# Sheet1.net
KiCad netlist of a schematic drawn in Altium Designer
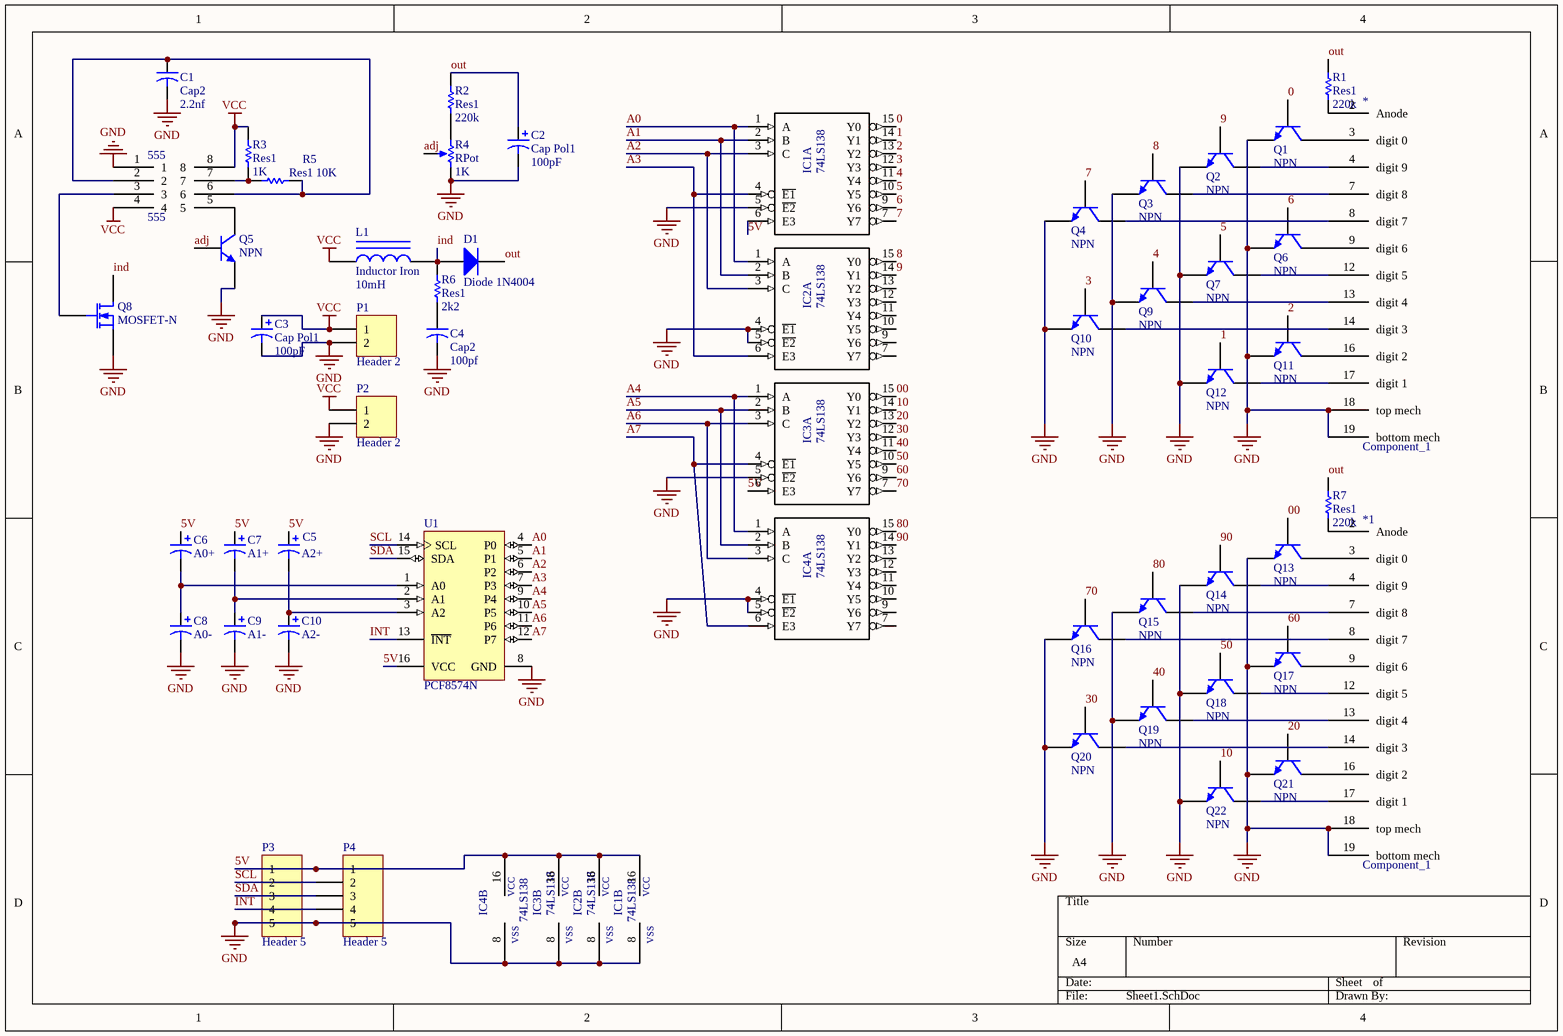
[diagram p0: Sheet1.SchDoc]

(export (version "E")
  (design (tool "Eeschema 10.0.6"))
  (components
    (comp (ref "*")
      (value "Component_1")
      (footprint "B8091")
      (libsource (lib "Schlib1") (part "Component_1"))
    )
    (comp (ref "*1")
      (value "Component_1")
      (footprint "B8091")
      (libsource (lib "Schlib1") (part "Component_1"))
    )
    (comp (ref "555") (value "555") (footprint "555") (libsource (lib "Schlib1") (part "555")))
    (comp (ref "C1")
      (value "Cap2")
      (footprint "CAPR5-4X5")
      (description "Capacitor")
      (fields (field (name "ALTIUM_VALUE") "2.2nf") (field (name "PUBLISHER") "Altium Limited"))
      (libsource (lib "Miscellaneous Devices") (part "Cap2"))
    )
    (comp (ref "C2")
      (value "Cap Pol1")
      (footprint "RB7.6-15")
      (description "Polarized Capacitor (Radial)")
      (fields (field (name "ALTIUM_VALUE") "100pF") (field (name "PUBLISHER") "Altium Limited"))
      (libsource (lib "Miscellaneous Devices") (part "Cap Pol1"))
    )
    (comp (ref "C3")
      (value "Cap Pol1")
      (footprint "RB7.6-15")
      (description "Polarized Capacitor (Radial)")
      (fields (field (name "ALTIUM_VALUE") "100pF") (field (name "PUBLISHER") "Altium Limited"))
      (libsource (lib "Miscellaneous Devices") (part "Cap Pol1"))
    )
    (comp (ref "C4")
      (value "Cap2")
      (footprint "CAPR5-4X5")
      (description "Capacitor")
      (fields (field (name "ALTIUM_VALUE") "100pf") (field (name "PUBLISHER") "Altium Limited"))
      (libsource (lib "Miscellaneous Devices") (part "Cap2"))
    )
    (comp (ref "C5")
      (value "A2+")
      (footprint "C0805")
      (description "Polarized Capacitor (Surface Mount)")
      (fields (field (name "PUBLISHER") "Altium Limited"))
      (libsource (lib "Miscellaneous Devices") (part "Cap Pol3"))
    )
    (comp (ref "C6")
      (value "A0+")
      (footprint "C0805")
      (description "Polarized Capacitor (Surface Mount)")
      (fields (field (name "PUBLISHER") "Altium Limited"))
      (libsource (lib "Miscellaneous Devices") (part "Cap Pol3"))
    )
    (comp (ref "C7")
      (value "A1+")
      (footprint "C0805")
      (description "Polarized Capacitor (Surface Mount)")
      (fields (field (name "PUBLISHER") "Altium Limited"))
      (libsource (lib "Miscellaneous Devices") (part "Cap Pol3"))
    )
    (comp (ref "C8")
      (value "A0-")
      (footprint "C0805")
      (description "Polarized Capacitor (Surface Mount)")
      (fields (field (name "PUBLISHER") "Altium Limited"))
      (libsource (lib "Miscellaneous Devices") (part "Cap Pol3"))
    )
    (comp (ref "C9")
      (value "A1-")
      (footprint "C0805")
      (description "Polarized Capacitor (Surface Mount)")
      (fields (field (name "PUBLISHER") "Altium Limited"))
      (libsource (lib "Miscellaneous Devices") (part "Cap Pol3"))
    )
    (comp (ref "C10")
      (value "A2-")
      (footprint "C0805")
      (description "Polarized Capacitor (Surface Mount)")
      (fields (field (name "PUBLISHER") "Altium Limited"))
      (libsource (lib "Miscellaneous Devices") (part "Cap Pol3"))
    )
    (comp (ref "D1")
      (value "Diode 1N4004")
      (footprint "DO-41")
      (description "1 Amp General Purpose Rectifier")
      (fields (field (name "PUBLISHER") "Altium Limited"))
      (libsource (lib "Miscellaneous Devices") (part "Diode 1N4004"))
    )
    (comp (ref "IC1")
      (value "74LS138")
      (footprint "DIP-16")
      (fields (field (name "MF") "Texas Instruments"))
      (libsource (lib "74LS138") (part "74LS138"))
    )
    (comp (ref "IC2")
      (value "74LS138")
      (footprint "DIP-16")
      (fields (field (name "MF") "Texas Instruments"))
      (libsource (lib "74LS138") (part "74LS138"))
    )
    (comp (ref "IC3")
      (value "74LS138")
      (footprint "DIP-16")
      (fields (field (name "MF") "Texas Instruments"))
      (libsource (lib "74LS138") (part "74LS138"))
    )
    (comp (ref "IC4")
      (value "74LS138")
      (footprint "DIP-16")
      (fields (field (name "MF") "Texas Instruments"))
      (libsource (lib "74LS138") (part "74LS138"))
    )
    (comp (ref "L1")
      (value "Inductor Iron")
      (footprint "AXIAL-0.5")
      (description "Magnetic-Core Inductor")
      (fields (field (name "ALTIUM_VALUE") "10mH") (field (name "PUBLISHER") "Altium Limited"))
      (libsource (lib "Miscellaneous Devices") (part "Inductor Iron"))
    )
    (comp (ref "P1")
      (value "Header 2")
      (footprint "HDR1X2")
      (description "Header, 2-Pin")
      (fields (field (name "PUBLISHER") "Altium Limited"))
      (libsource (lib "Miscellaneous Connectors") (part "Header 2"))
    )
    (comp (ref "P2")
      (value "Header 2")
      (footprint "HDR1X2")
      (description "Header, 2-Pin")
      (fields (field (name "PUBLISHER") "Altium Limited"))
      (libsource (lib "Miscellaneous Connectors") (part "Header 2"))
    )
    (comp (ref "P3")
      (value "Header 5")
      (footprint "HDR1X5")
      (description "Header, 5-Pin")
      (fields (field (name "PUBLISHER") "Altium Limited"))
      (libsource (lib "Miscellaneous Connectors") (part "Header 5"))
    )
    (comp (ref "P4")
      (value "Header 5")
      (footprint "HDR1X5")
      (description "Header, 5-Pin")
      (fields (field (name "PUBLISHER") "Altium Limited"))
      (libsource (lib "Miscellaneous Connectors") (part "Header 5"))
    )
    (comp (ref "Q1")
      (value "NPN")
      (footprint "TO-226-AA")
      (description "NPN Bipolar Transistor")
      (fields (field (name "PUBLISHER") "Altium Limited"))
      (libsource (lib "Miscellaneous Devices") (part "NPN"))
    )
    (comp (ref "Q2")
      (value "NPN")
      (footprint "TO-226-AA")
      (description "NPN Bipolar Transistor")
      (fields (field (name "PUBLISHER") "Altium Limited"))
      (libsource (lib "Miscellaneous Devices") (part "NPN"))
    )
    (comp (ref "Q3")
      (value "NPN")
      (footprint "TO-226-AA")
      (description "NPN Bipolar Transistor")
      (fields (field (name "PUBLISHER") "Altium Limited"))
      (libsource (lib "Miscellaneous Devices") (part "NPN"))
    )
    (comp (ref "Q4")
      (value "NPN")
      (footprint "TO-226-AA")
      (description "NPN Bipolar Transistor")
      (fields (field (name "PUBLISHER") "Altium Limited"))
      (libsource (lib "Miscellaneous Devices") (part "NPN"))
    )
    (comp (ref "Q5")
      (value "NPN")
      (footprint "TO-226-AA")
      (description "NPN Bipolar Transistor")
      (fields (field (name "PUBLISHER") "Altium Limited"))
      (libsource (lib "Miscellaneous Devices") (part "NPN"))
    )
    (comp (ref "Q6")
      (value "NPN")
      (footprint "TO-226-AA")
      (description "NPN Bipolar Transistor")
      (fields (field (name "PUBLISHER") "Altium Limited"))
      (libsource (lib "Miscellaneous Devices") (part "NPN"))
    )
    (comp (ref "Q7")
      (value "NPN")
      (footprint "TO-226-AA")
      (description "NPN Bipolar Transistor")
      (fields (field (name "PUBLISHER") "Altium Limited"))
      (libsource (lib "Miscellaneous Devices") (part "NPN"))
    )
    (comp (ref "Q8")
      (value "MOSFET-N")
      (footprint "E3")
      (description "N-Channel MOSFET")
      (fields (field (name "PUBLISHER") "Altium Limited"))
      (libsource (lib "Miscellaneous Devices") (part "MOSFET-N"))
    )
    (comp (ref "Q9")
      (value "NPN")
      (footprint "TO-226-AA")
      (description "NPN Bipolar Transistor")
      (fields (field (name "PUBLISHER") "Altium Limited"))
      (libsource (lib "Miscellaneous Devices") (part "NPN"))
    )
    (comp (ref "Q10")
      (value "NPN")
      (footprint "TO-226-AA")
      (description "NPN Bipolar Transistor")
      (fields (field (name "PUBLISHER") "Altium Limited"))
      (libsource (lib "Miscellaneous Devices") (part "NPN"))
    )
    (comp (ref "Q11")
      (value "NPN")
      (footprint "TO-226-AA")
      (description "NPN Bipolar Transistor")
      (fields (field (name "PUBLISHER") "Altium Limited"))
      (libsource (lib "Miscellaneous Devices") (part "NPN"))
    )
    (comp (ref "Q12")
      (value "NPN")
      (footprint "TO-226-AA")
      (description "NPN Bipolar Transistor")
      (fields (field (name "PUBLISHER") "Altium Limited"))
      (libsource (lib "Miscellaneous Devices") (part "NPN"))
    )
    (comp (ref "Q13")
      (value "NPN")
      (footprint "TO-226-AA")
      (description "NPN Bipolar Transistor")
      (fields (field (name "PUBLISHER") "Altium Limited"))
      (libsource (lib "Miscellaneous Devices") (part "NPN"))
    )
    (comp (ref "Q14")
      (value "NPN")
      (footprint "TO-226-AA")
      (description "NPN Bipolar Transistor")
      (fields (field (name "PUBLISHER") "Altium Limited"))
      (libsource (lib "Miscellaneous Devices") (part "NPN"))
    )
    (comp (ref "Q15")
      (value "NPN")
      (footprint "TO-226-AA")
      (description "NPN Bipolar Transistor")
      (fields (field (name "PUBLISHER") "Altium Limited"))
      (libsource (lib "Miscellaneous Devices") (part "NPN"))
    )
    (comp (ref "Q16")
      (value "NPN")
      (footprint "TO-226-AA")
      (description "NPN Bipolar Transistor")
      (fields (field (name "PUBLISHER") "Altium Limited"))
      (libsource (lib "Miscellaneous Devices") (part "NPN"))
    )
    (comp (ref "Q17")
      (value "NPN")
      (footprint "TO-226-AA")
      (description "NPN Bipolar Transistor")
      (fields (field (name "PUBLISHER") "Altium Limited"))
      (libsource (lib "Miscellaneous Devices") (part "NPN"))
    )
    (comp (ref "Q18")
      (value "NPN")
      (footprint "TO-226-AA")
      (description "NPN Bipolar Transistor")
      (fields (field (name "PUBLISHER") "Altium Limited"))
      (libsource (lib "Miscellaneous Devices") (part "NPN"))
    )
    (comp (ref "Q19")
      (value "NPN")
      (footprint "TO-226-AA")
      (description "NPN Bipolar Transistor")
      (fields (field (name "PUBLISHER") "Altium Limited"))
      (libsource (lib "Miscellaneous Devices") (part "NPN"))
    )
    (comp (ref "Q20")
      (value "NPN")
      (footprint "TO-226-AA")
      (description "NPN Bipolar Transistor")
      (fields (field (name "PUBLISHER") "Altium Limited"))
      (libsource (lib "Miscellaneous Devices") (part "NPN"))
    )
    (comp (ref "Q21")
      (value "NPN")
      (footprint "TO-226-AA")
      (description "NPN Bipolar Transistor")
      (fields (field (name "PUBLISHER") "Altium Limited"))
      (libsource (lib "Miscellaneous Devices") (part "NPN"))
    )
    (comp (ref "Q22")
      (value "NPN")
      (footprint "TO-226-AA")
      (description "NPN Bipolar Transistor")
      (fields (field (name "PUBLISHER") "Altium Limited"))
      (libsource (lib "Miscellaneous Devices") (part "NPN"))
    )
    (comp (ref "R1")
      (value "Res1")
      (footprint "AXIAL-0.3")
      (description "Resistor")
      (fields (field (name "ALTIUM_VALUE") "220k") (field (name "PUBLISHER") "Altium Limited"))
      (libsource (lib "Miscellaneous Devices") (part "Res1"))
    )
    (comp (ref "R2")
      (value "Res1")
      (footprint "AXIAL-0.3")
      (description "Resistor")
      (fields (field (name "ALTIUM_VALUE") "220k") (field (name "PUBLISHER") "Altium Limited"))
      (libsource (lib "Miscellaneous Devices") (part "Res1"))
    )
    (comp (ref "R3")
      (value "Res1")
      (footprint "AXIAL-0.3")
      (description "Resistor")
      (fields (field (name "ALTIUM_VALUE") "1K") (field (name "PUBLISHER") "Altium Limited"))
      (libsource (lib "Miscellaneous Devices") (part "Res1"))
    )
    (comp (ref "R4")
      (value "RPot")
      (footprint "VR5")
      (description "Potentiometer")
      (fields (field (name "ALTIUM_VALUE") "1K") (field (name "PUBLISHER") "Altium Limited"))
      (libsource (lib "Miscellaneous Devices") (part "RPot"))
    )
    (comp (ref "R5")
      (value "Res1")
      (footprint "AXIAL-0.3")
      (description "Resistor")
      (fields (field (name "ALTIUM_VALUE") "10K") (field (name "PUBLISHER") "Altium Limited"))
      (libsource (lib "Miscellaneous Devices") (part "Res1"))
    )
    (comp (ref "R6")
      (value "Res1")
      (footprint "AXIAL-0.3")
      (description "Resistor")
      (fields (field (name "ALTIUM_VALUE") "2k2") (field (name "PUBLISHER") "Altium Limited"))
      (libsource (lib "Miscellaneous Devices") (part "Res1"))
    )
    (comp (ref "R7")
      (value "Res1")
      (footprint "AXIAL-0.3")
      (description "Resistor")
      (fields (field (name "ALTIUM_VALUE") "220k") (field (name "PUBLISHER") "Altium Limited"))
      (libsource (lib "Miscellaneous Devices") (part "Res1"))
    )
    (comp (ref "U1")
      (value "PCF8574N")
      (footprint "N0016A")
      (description "Remote 8-Bit I/O Expander for I2C-Bus, 2.5 to 6 V, -40 to 85 degC, 16-pin PDIP (N), Pb-Free (RoHS)")
      (fields (field (name "MANUFACTURER") "Texas Instruments"))
      (libsource (lib "Altium Content Vault") (part "CMP-0314-00016-2"))
    )
  )
  (nets
    (net (code "1") (name "/0") (class "Default")
      (node (ref "IC1") (pin "15") (pinfunction "Y0_15") (pintype "output"))
      (node (ref "Q1") (pin "2") (pinfunction "B_2") (pintype "passive"))
    )
    (net (code "2") (name "/00") (class "Default")
      (node (ref "IC3") (pin "15") (pinfunction "Y0_15") (pintype "output"))
      (node (ref "Q13") (pin "2") (pinfunction "B_2") (pintype "passive"))
    )
    (net (code "3") (name "/1") (class "Default")
      (node (ref "IC1") (pin "14") (pinfunction "Y1_14") (pintype "output"))
      (node (ref "Q12") (pin "2") (pinfunction "B_2") (pintype "passive"))
    )
    (net (code "4") (name "/2") (class "Default")
      (node (ref "IC1") (pin "13") (pinfunction "Y2_13") (pintype "output"))
      (node (ref "Q11") (pin "2") (pinfunction "B_2") (pintype "passive"))
    )
    (net (code "5") (name "/3") (class "Default")
      (node (ref "IC1") (pin "12") (pinfunction "Y3_12") (pintype "output"))
      (node (ref "Q10") (pin "2") (pinfunction "B_2") (pintype "passive"))
    )
    (net (code "6") (name "/4") (class "Default")
      (node (ref "IC1") (pin "11") (pinfunction "Y4_11") (pintype "output"))
      (node (ref "Q9") (pin "2") (pinfunction "B_2") (pintype "passive"))
    )
    (net (code "7") (name "/5") (class "Default")
      (node (ref "IC1") (pin "10") (pinfunction "Y5_10") (pintype "output"))
      (node (ref "Q7") (pin "2") (pinfunction "B_2") (pintype "passive"))
    )
    (net (code "8") (name "/5V") (class "Default")
      (node (ref "C5") (pin "1") (pinfunction "1_1") (pintype "passive"))
      (node (ref "C6") (pin "1") (pinfunction "1_1") (pintype "passive"))
      (node (ref "C7") (pin "1") (pinfunction "1_1") (pintype "passive"))
      (node (ref "IC1") (pin "16") (pinfunction "VCC_16") (pintype "power_in"))
      (node (ref "IC1") (pin "6") (pinfunction "E3_6") (pintype "input"))
      (node (ref "IC2") (pin "16") (pinfunction "VCC_16") (pintype "power_in"))
      (node (ref "IC3") (pin "16") (pinfunction "VCC_16") (pintype "power_in"))
      (node (ref "IC3") (pin "6") (pinfunction "E3_6") (pintype "input"))
      (node (ref "IC4") (pin "16") (pinfunction "VCC_16") (pintype "power_in"))
      (node (ref "P3") (pin "1") (pinfunction "1_1") (pintype "passive"))
      (node (ref "P4") (pin "1") (pinfunction "1_1") (pintype "passive"))
      (node (ref "U1") (pin "16") (pinfunction "VCC_16") (pintype "power_in"))
    )
    (net (code "9") (name "/6") (class "Default")
      (node (ref "IC1") (pin "9") (pinfunction "Y6_9") (pintype "output"))
      (node (ref "Q6") (pin "2") (pinfunction "B_2") (pintype "passive"))
    )
    (net (code "10") (name "/7") (class "Default")
      (node (ref "IC1") (pin "7") (pinfunction "Y7_7") (pintype "output"))
      (node (ref "Q4") (pin "2") (pinfunction "B_2") (pintype "passive"))
    )
    (net (code "11") (name "/8") (class "Default")
      (node (ref "IC2") (pin "15") (pinfunction "Y0_15") (pintype "output"))
      (node (ref "Q3") (pin "2") (pinfunction "B_2") (pintype "passive"))
    )
    (net (code "12") (name "/9") (class "Default")
      (node (ref "IC2") (pin "14") (pinfunction "Y1_14") (pintype "output"))
      (node (ref "Q2") (pin "2") (pinfunction "B_2") (pintype "passive"))
    )
    (net (code "13") (name "/10") (class "Default")
      (node (ref "IC3") (pin "14") (pinfunction "Y1_14") (pintype "output"))
      (node (ref "Q22") (pin "2") (pinfunction "B_2") (pintype "passive"))
    )
    (net (code "14") (name "/20") (class "Default")
      (node (ref "IC3") (pin "13") (pinfunction "Y2_13") (pintype "output"))
      (node (ref "Q21") (pin "2") (pinfunction "B_2") (pintype "passive"))
    )
    (net (code "15") (name "/30") (class "Default")
      (node (ref "IC3") (pin "12") (pinfunction "Y3_12") (pintype "output"))
      (node (ref "Q20") (pin "2") (pinfunction "B_2") (pintype "passive"))
    )
    (net (code "16") (name "/40") (class "Default")
      (node (ref "IC3") (pin "11") (pinfunction "Y4_11") (pintype "output"))
      (node (ref "Q19") (pin "2") (pinfunction "B_2") (pintype "passive"))
    )
    (net (code "17") (name "/50") (class "Default")
      (node (ref "IC3") (pin "10") (pinfunction "Y5_10") (pintype "output"))
      (node (ref "Q18") (pin "2") (pinfunction "B_2") (pintype "passive"))
    )
    (net (code "18") (name "/60") (class "Default")
      (node (ref "IC3") (pin "9") (pinfunction "Y6_9") (pintype "output"))
      (node (ref "Q17") (pin "2") (pinfunction "B_2") (pintype "passive"))
    )
    (net (code "19") (name "/70") (class "Default")
      (node (ref "IC3") (pin "7") (pinfunction "Y7_7") (pintype "output"))
      (node (ref "Q16") (pin "2") (pinfunction "B_2") (pintype "passive"))
    )
    (net (code "20") (name "/80") (class "Default")
      (node (ref "IC4") (pin "15") (pinfunction "Y0_15") (pintype "output"))
      (node (ref "Q15") (pin "2") (pinfunction "B_2") (pintype "passive"))
    )
    (net (code "21") (name "/90") (class "Default")
      (node (ref "IC4") (pin "14") (pinfunction "Y1_14") (pintype "output"))
      (node (ref "Q14") (pin "2") (pinfunction "B_2") (pintype "passive"))
    )
    (net (code "22") (name "/A0") (class "Default")
      (node (ref "IC1") (pin "1") (pinfunction "A_1") (pintype "input"))
      (node (ref "IC2") (pin "1") (pinfunction "A_1") (pintype "input"))
      (node (ref "U1") (pin "4") (pinfunction "P0_4") (pintype "bidirectional"))
    )
    (net (code "23") (name "/A1") (class "Default")
      (node (ref "IC1") (pin "2") (pinfunction "B_2") (pintype "input"))
      (node (ref "IC2") (pin "2") (pinfunction "B_2") (pintype "input"))
      (node (ref "U1") (pin "5") (pinfunction "P1_5") (pintype "bidirectional"))
    )
    (net (code "24") (name "/A2") (class "Default")
      (node (ref "IC1") (pin "3") (pinfunction "C_3") (pintype "input"))
      (node (ref "IC2") (pin "3") (pinfunction "C_3") (pintype "input"))
      (node (ref "U1") (pin "6") (pinfunction "P2_6") (pintype "bidirectional"))
    )
    (net (code "25") (name "/A3") (class "Default")
      (node (ref "IC1") (pin "4") (pinfunction "~{E1}_4") (pintype "input"))
      (node (ref "IC2") (pin "6") (pinfunction "E3_6") (pintype "input"))
      (node (ref "U1") (pin "7") (pinfunction "P3_7") (pintype "bidirectional"))
    )
    (net (code "26") (name "/A4") (class "Default")
      (node (ref "IC3") (pin "1") (pinfunction "A_1") (pintype "input"))
      (node (ref "IC4") (pin "1") (pinfunction "A_1") (pintype "input"))
      (node (ref "U1") (pin "9") (pinfunction "P4_9") (pintype "bidirectional"))
    )
    (net (code "27") (name "/A5") (class "Default")
      (node (ref "IC3") (pin "2") (pinfunction "B_2") (pintype "input"))
      (node (ref "IC4") (pin "2") (pinfunction "B_2") (pintype "input"))
      (node (ref "U1") (pin "10") (pinfunction "P5_10") (pintype "bidirectional"))
    )
    (net (code "28") (name "/A6") (class "Default")
      (node (ref "IC3") (pin "3") (pinfunction "C_3") (pintype "input"))
      (node (ref "IC4") (pin "3") (pinfunction "C_3") (pintype "input"))
      (node (ref "U1") (pin "11") (pinfunction "P6_11") (pintype "bidirectional"))
    )
    (net (code "29") (name "/A7") (class "Default")
      (node (ref "IC3") (pin "4") (pinfunction "~{E1}_4") (pintype "input"))
      (node (ref "IC4") (pin "6") (pinfunction "E3_6") (pintype "input"))
      (node (ref "U1") (pin "12") (pinfunction "P7_12") (pintype "bidirectional"))
    )
    (net (code "30") (name "/INT") (class "Default")
      (node (ref "P3") (pin "4") (pinfunction "4_4") (pintype "passive"))
      (node (ref "P4") (pin "4") (pinfunction "4_4") (pintype "passive"))
      (node (ref "U1") (pin "13") (pinfunction "~{INT}_13") (pintype "open_collector"))
    )
    (net (code "31") (name "/SCL") (class "Default")
      (node (ref "P3") (pin "2") (pinfunction "2_2") (pintype "passive"))
      (node (ref "P4") (pin "2") (pinfunction "2_2") (pintype "passive"))
      (node (ref "U1") (pin "14") (pinfunction "SCL_14") (pintype "input"))
    )
    (net (code "32") (name "/SDA") (class "Default")
      (node (ref "P3") (pin "3") (pinfunction "3_3") (pintype "passive"))
      (node (ref "P4") (pin "3") (pinfunction "3_3") (pintype "passive"))
      (node (ref "U1") (pin "15") (pinfunction "SDA_15") (pintype "bidirectional"))
    )
    (net (code "33") (name "/adj") (class "Default")
      (node (ref "Q5") (pin "2") (pinfunction "B_2") (pintype "passive"))
      (node (ref "R4") (pin "3") (pinfunction "TAP_3") (pintype "passive"))
    )
    (net (code "34") (name "/ind") (class "Default")
      (node (ref "D1") (pin "1") (pinfunction "A_1") (pintype "passive"))
      (node (ref "L1") (pin "2") (pinfunction "2_2") (pintype "passive"))
      (node (ref "Q8") (pin "1") (pinfunction "D_1") (pintype "passive"))
      (node (ref "R6") (pin "2") (pinfunction "2_2") (pintype "passive"))
    )
    (net (code "35") (name "/out") (class "Default")
      (node (ref "C2") (pin "1") (pinfunction "1_1") (pintype "passive"))
      (node (ref "D1") (pin "2") (pinfunction "K_2") (pintype "passive"))
      (node (ref "R1") (pin "2") (pinfunction "2_2") (pintype "passive"))
      (node (ref "R2") (pin "2") (pinfunction "2_2") (pintype "passive"))
      (node (ref "R7") (pin "2") (pinfunction "2_2") (pintype "passive"))
    )
    (net (code "36") (name "GND") (class "Default")
      (node (ref "*") (pin "18") (pinfunction "top_mech_18") (pintype "passive"))
      (node (ref "*") (pin "19") (pinfunction "bottom_mech_19") (pintype "passive"))
      (node (ref "*1") (pin "18") (pinfunction "top_mech_18") (pintype "passive"))
      (node (ref "*1") (pin "19") (pinfunction "bottom_mech_19") (pintype "passive"))
      (node (ref "555") (pin "1") (pinfunction "1_1") (pintype "passive"))
      (node (ref "C1") (pin "2") (pinfunction "2_2") (pintype "passive"))
      (node (ref "C10") (pin "2") (pinfunction "2_2") (pintype "passive"))
      (node (ref "C2") (pin "2") (pinfunction "2_2") (pintype "passive"))
      (node (ref "C3") (pin "2") (pinfunction "2_2") (pintype "passive"))
      (node (ref "C4") (pin "2") (pinfunction "2_2") (pintype "passive"))
      (node (ref "C8") (pin "2") (pinfunction "2_2") (pintype "passive"))
      (node (ref "C9") (pin "2") (pinfunction "2_2") (pintype "passive"))
      (node (ref "IC1") (pin "5") (pinfunction "~{E2}_5") (pintype "input"))
      (node (ref "IC1") (pin "8") (pinfunction "VSS_8") (pintype "power_in"))
      (node (ref "IC2") (pin "4") (pinfunction "~{E1}_4") (pintype "input"))
      (node (ref "IC2") (pin "5") (pinfunction "~{E2}_5") (pintype "input"))
      (node (ref "IC2") (pin "8") (pinfunction "VSS_8") (pintype "power_in"))
      (node (ref "IC3") (pin "5") (pinfunction "~{E2}_5") (pintype "input"))
      (node (ref "IC3") (pin "8") (pinfunction "VSS_8") (pintype "power_in"))
      (node (ref "IC4") (pin "4") (pinfunction "~{E1}_4") (pintype "input"))
      (node (ref "IC4") (pin "5") (pinfunction "~{E2}_5") (pintype "input"))
      (node (ref "IC4") (pin "8") (pinfunction "VSS_8") (pintype "power_in"))
      (node (ref "P1") (pin "2") (pinfunction "2_2") (pintype "passive"))
      (node (ref "P2") (pin "2") (pinfunction "2_2") (pintype "passive"))
      (node (ref "P3") (pin "5") (pinfunction "5_5") (pintype "passive"))
      (node (ref "P4") (pin "5") (pinfunction "5_5") (pintype "passive"))
      (node (ref "Q1") (pin "3") (pinfunction "E_3") (pintype "passive"))
      (node (ref "Q10") (pin "3") (pinfunction "E_3") (pintype "passive"))
      (node (ref "Q11") (pin "3") (pinfunction "E_3") (pintype "passive"))
      (node (ref "Q12") (pin "3") (pinfunction "E_3") (pintype "passive"))
      (node (ref "Q13") (pin "3") (pinfunction "E_3") (pintype "passive"))
      (node (ref "Q14") (pin "3") (pinfunction "E_3") (pintype "passive"))
      (node (ref "Q15") (pin "3") (pinfunction "E_3") (pintype "passive"))
      (node (ref "Q16") (pin "3") (pinfunction "E_3") (pintype "passive"))
      (node (ref "Q17") (pin "3") (pinfunction "E_3") (pintype "passive"))
      (node (ref "Q18") (pin "3") (pinfunction "E_3") (pintype "passive"))
      (node (ref "Q19") (pin "3") (pinfunction "E_3") (pintype "passive"))
      (node (ref "Q2") (pin "3") (pinfunction "E_3") (pintype "passive"))
      (node (ref "Q20") (pin "3") (pinfunction "E_3") (pintype "passive"))
      (node (ref "Q21") (pin "3") (pinfunction "E_3") (pintype "passive"))
      (node (ref "Q22") (pin "3") (pinfunction "E_3") (pintype "passive"))
      (node (ref "Q3") (pin "3") (pinfunction "E_3") (pintype "passive"))
      (node (ref "Q4") (pin "3") (pinfunction "E_3") (pintype "passive"))
      (node (ref "Q5") (pin "3") (pinfunction "E_3") (pintype "passive"))
      (node (ref "Q6") (pin "3") (pinfunction "E_3") (pintype "passive"))
      (node (ref "Q7") (pin "3") (pinfunction "E_3") (pintype "passive"))
      (node (ref "Q8") (pin "3") (pinfunction "S_3") (pintype "passive"))
      (node (ref "Q9") (pin "3") (pinfunction "E_3") (pintype "passive"))
      (node (ref "R4") (pin "2") (pinfunction "BOT_2") (pintype "passive"))
      (node (ref "U1") (pin "8") (pinfunction "GND_8") (pintype "power_in"))
    )
    (net (code "37") (name "Net-(*-Anode)") (class "Default")
      (node (ref "*") (pin "2") (pinfunction "Anode_2") (pintype "passive"))
      (node (ref "R1") (pin "1") (pinfunction "1_1") (pintype "passive"))
    )
    (net (code "38") (name "Net-(*-digit_0)") (class "Default")
      (node (ref "*") (pin "3") (pinfunction "digit_0_3") (pintype "passive"))
      (node (ref "Q1") (pin "1") (pinfunction "C_1") (pintype "passive"))
    )
    (net (code "39") (name "Net-(*-digit_1)") (class "Default")
      (node (ref "*") (pin "17") (pinfunction "digit_1_17") (pintype "passive"))
      (node (ref "Q12") (pin "1") (pinfunction "C_1") (pintype "passive"))
    )
    (net (code "40") (name "Net-(*-digit_2)") (class "Default")
      (node (ref "*") (pin "16") (pinfunction "digit_2_16") (pintype "passive"))
      (node (ref "Q11") (pin "1") (pinfunction "C_1") (pintype "passive"))
    )
    (net (code "41") (name "Net-(*-digit_3)") (class "Default")
      (node (ref "*") (pin "14") (pinfunction "digit_3_14") (pintype "passive"))
      (node (ref "Q10") (pin "1") (pinfunction "C_1") (pintype "passive"))
    )
    (net (code "42") (name "Net-(*-digit_4)") (class "Default")
      (node (ref "*") (pin "13") (pinfunction "digit_4_13") (pintype "passive"))
      (node (ref "Q9") (pin "1") (pinfunction "C_1") (pintype "passive"))
    )
    (net (code "43") (name "Net-(*-digit_5)") (class "Default")
      (node (ref "*") (pin "12") (pinfunction "digit_5_12") (pintype "passive"))
      (node (ref "Q7") (pin "1") (pinfunction "C_1") (pintype "passive"))
    )
    (net (code "44") (name "Net-(*-digit_6)") (class "Default")
      (node (ref "*") (pin "9") (pinfunction "digit_6_9") (pintype "passive"))
      (node (ref "Q6") (pin "1") (pinfunction "C_1") (pintype "passive"))
    )
    (net (code "45") (name "Net-(*-digit_7)") (class "Default")
      (node (ref "*") (pin "8") (pinfunction "digit_7_8") (pintype "passive"))
      (node (ref "Q4") (pin "1") (pinfunction "C_1") (pintype "passive"))
    )
    (net (code "46") (name "Net-(*-digit_8)") (class "Default")
      (node (ref "*") (pin "7") (pinfunction "digit_8_7") (pintype "passive"))
      (node (ref "Q3") (pin "1") (pinfunction "C_1") (pintype "passive"))
    )
    (net (code "47") (name "Net-(*-digit_9)") (class "Default")
      (node (ref "*") (pin "4") (pinfunction "digit_9_4") (pintype "passive"))
      (node (ref "Q2") (pin "1") (pinfunction "C_1") (pintype "passive"))
    )
    (net (code "48") (name "Net-(*1-Anode)") (class "Default")
      (node (ref "*1") (pin "2") (pinfunction "Anode_2") (pintype "passive"))
      (node (ref "R7") (pin "1") (pinfunction "1_1") (pintype "passive"))
    )
    (net (code "49") (name "Net-(*1-digit_0)") (class "Default")
      (node (ref "*1") (pin "3") (pinfunction "digit_0_3") (pintype "passive"))
      (node (ref "Q13") (pin "1") (pinfunction "C_1") (pintype "passive"))
    )
    (net (code "50") (name "Net-(*1-digit_1)") (class "Default")
      (node (ref "*1") (pin "17") (pinfunction "digit_1_17") (pintype "passive"))
      (node (ref "Q22") (pin "1") (pinfunction "C_1") (pintype "passive"))
    )
    (net (code "51") (name "Net-(*1-digit_2)") (class "Default")
      (node (ref "*1") (pin "16") (pinfunction "digit_2_16") (pintype "passive"))
      (node (ref "Q21") (pin "1") (pinfunction "C_1") (pintype "passive"))
    )
    (net (code "52") (name "Net-(*1-digit_3)") (class "Default")
      (node (ref "*1") (pin "14") (pinfunction "digit_3_14") (pintype "passive"))
      (node (ref "Q20") (pin "1") (pinfunction "C_1") (pintype "passive"))
    )
    (net (code "53") (name "Net-(*1-digit_4)") (class "Default")
      (node (ref "*1") (pin "13") (pinfunction "digit_4_13") (pintype "passive"))
      (node (ref "Q19") (pin "1") (pinfunction "C_1") (pintype "passive"))
    )
    (net (code "54") (name "Net-(*1-digit_5)") (class "Default")
      (node (ref "*1") (pin "12") (pinfunction "digit_5_12") (pintype "passive"))
      (node (ref "Q18") (pin "1") (pinfunction "C_1") (pintype "passive"))
    )
    (net (code "55") (name "Net-(*1-digit_6)") (class "Default")
      (node (ref "*1") (pin "9") (pinfunction "digit_6_9") (pintype "passive"))
      (node (ref "Q17") (pin "1") (pinfunction "C_1") (pintype "passive"))
    )
    (net (code "56") (name "Net-(*1-digit_7)") (class "Default")
      (node (ref "*1") (pin "8") (pinfunction "digit_7_8") (pintype "passive"))
      (node (ref "Q16") (pin "1") (pinfunction "C_1") (pintype "passive"))
    )
    (net (code "57") (name "Net-(*1-digit_8)") (class "Default")
      (node (ref "*1") (pin "7") (pinfunction "digit_8_7") (pintype "passive"))
      (node (ref "Q15") (pin "1") (pinfunction "C_1") (pintype "passive"))
    )
    (net (code "58") (name "Net-(*1-digit_9)") (class "Default")
      (node (ref "*1") (pin "4") (pinfunction "digit_9_4") (pintype "passive"))
      (node (ref "Q14") (pin "1") (pinfunction "C_1") (pintype "passive"))
    )
    (net (code "59") (name "Net-(555-Pad2)") (class "Default")
      (node (ref "555") (pin "2") (pinfunction "2_2") (pintype "passive"))
      (node (ref "555") (pin "6") (pinfunction "6_6") (pintype "passive"))
      (node (ref "C1") (pin "1") (pinfunction "1_1") (pintype "passive"))
      (node (ref "R5") (pin "1") (pinfunction "1_1") (pintype "passive"))
    )
    (net (code "60") (name "Net-(555-Pad7)") (class "Default")
      (node (ref "555") (pin "7") (pinfunction "7_7") (pintype "passive"))
      (node (ref "R3") (pin "1") (pinfunction "1_1") (pintype "passive"))
      (node (ref "R5") (pin "2") (pinfunction "2_2") (pintype "passive"))
    )
    (net (code "61") (name "Net-(C4-Pad1)") (class "Default")
      (node (ref "C4") (pin "1") (pinfunction "1_1") (pintype "passive"))
      (node (ref "R6") (pin "1") (pinfunction "1_1") (pintype "passive"))
    )
    (net (code "62") (name "Net-(Q5-C)") (class "Default")
      (node (ref "555") (pin "5") (pinfunction "5_5") (pintype "passive"))
      (node (ref "Q5") (pin "1") (pinfunction "C_1") (pintype "passive"))
    )
    (net (code "63") (name "Net-(Q8-G)") (class "Default")
      (node (ref "555") (pin "3") (pinfunction "3_3") (pintype "passive"))
      (node (ref "Q8") (pin "2") (pinfunction "G_2") (pintype "passive"))
    )
    (net (code "64") (name "Net-(R4-TOP)") (class "Default")
      (node (ref "R2") (pin "1") (pinfunction "1_1") (pintype "passive"))
      (node (ref "R4") (pin "1") (pinfunction "TOP_1") (pintype "passive"))
    )
    (net (code "65") (name "Net-(U1-A0)") (class "Default")
      (node (ref "C6") (pin "2") (pinfunction "2_2") (pintype "passive"))
      (node (ref "C8") (pin "1") (pinfunction "1_1") (pintype "passive"))
      (node (ref "U1") (pin "1") (pinfunction "A0_1") (pintype "input"))
    )
    (net (code "66") (name "Net-(U1-A1)") (class "Default")
      (node (ref "C7") (pin "2") (pinfunction "2_2") (pintype "passive"))
      (node (ref "C9") (pin "1") (pinfunction "1_1") (pintype "passive"))
      (node (ref "U1") (pin "2") (pinfunction "A1_2") (pintype "input"))
    )
    (net (code "67") (name "Net-(U1-A2)") (class "Default")
      (node (ref "C10") (pin "1") (pinfunction "1_1") (pintype "passive"))
      (node (ref "C5") (pin "2") (pinfunction "2_2") (pintype "passive"))
      (node (ref "U1") (pin "3") (pinfunction "A2_3") (pintype "input"))
    )
    (net (code "68") (name "VCC") (class "Default")
      (node (ref "555") (pin "4") (pinfunction "4_4") (pintype "passive"))
      (node (ref "555") (pin "8") (pinfunction "8_8") (pintype "passive"))
      (node (ref "C3") (pin "1") (pinfunction "1_1") (pintype "passive"))
      (node (ref "L1") (pin "1") (pinfunction "1_1") (pintype "passive"))
      (node (ref "P1") (pin "1") (pinfunction "1_1") (pintype "passive"))
      (node (ref "P2") (pin "1") (pinfunction "1_1") (pintype "passive"))
      (node (ref "R3") (pin "2") (pinfunction "2_2") (pintype "passive"))
    )
    (net (code "69") (name "unconnected-(IC2A-Y2-Pad13)") (class "Default")
      (node (ref "IC2") (pin "13") (pinfunction "Y2_13") (pintype "output"))
    )
    (net (code "70") (name "unconnected-(IC2A-Y3-Pad12)") (class "Default")
      (node (ref "IC2") (pin "12") (pinfunction "Y3_12") (pintype "output"))
    )
    (net (code "71") (name "unconnected-(IC2A-Y4-Pad11)") (class "Default")
      (node (ref "IC2") (pin "11") (pinfunction "Y4_11") (pintype "output"))
    )
    (net (code "72") (name "unconnected-(IC2A-Y5-Pad10)") (class "Default")
      (node (ref "IC2") (pin "10") (pinfunction "Y5_10") (pintype "output"))
    )
    (net (code "73") (name "unconnected-(IC2A-Y6-Pad9)") (class "Default")
      (node (ref "IC2") (pin "9") (pinfunction "Y6_9") (pintype "output"))
    )
    (net (code "74") (name "unconnected-(IC2A-Y7-Pad7)") (class "Default")
      (node (ref "IC2") (pin "7") (pinfunction "Y7_7") (pintype "output"))
    )
    (net (code "75") (name "unconnected-(IC4A-Y2-Pad13)") (class "Default")
      (node (ref "IC4") (pin "13") (pinfunction "Y2_13") (pintype "output"))
    )
    (net (code "76") (name "unconnected-(IC4A-Y3-Pad12)") (class "Default")
      (node (ref "IC4") (pin "12") (pinfunction "Y3_12") (pintype "output"))
    )
    (net (code "77") (name "unconnected-(IC4A-Y4-Pad11)") (class "Default")
      (node (ref "IC4") (pin "11") (pinfunction "Y4_11") (pintype "output"))
    )
    (net (code "78") (name "unconnected-(IC4A-Y5-Pad10)") (class "Default")
      (node (ref "IC4") (pin "10") (pinfunction "Y5_10") (pintype "output"))
    )
    (net (code "79") (name "unconnected-(IC4A-Y6-Pad9)") (class "Default")
      (node (ref "IC4") (pin "9") (pinfunction "Y6_9") (pintype "output"))
    )
    (net (code "80") (name "unconnected-(IC4A-Y7-Pad7)") (class "Default")
      (node (ref "IC4") (pin "7") (pinfunction "Y7_7") (pintype "output"))
    )
  )
)
